# sb-sonata-ethmac.net
KiCad netlist of a schematic drawn in Altium Designer
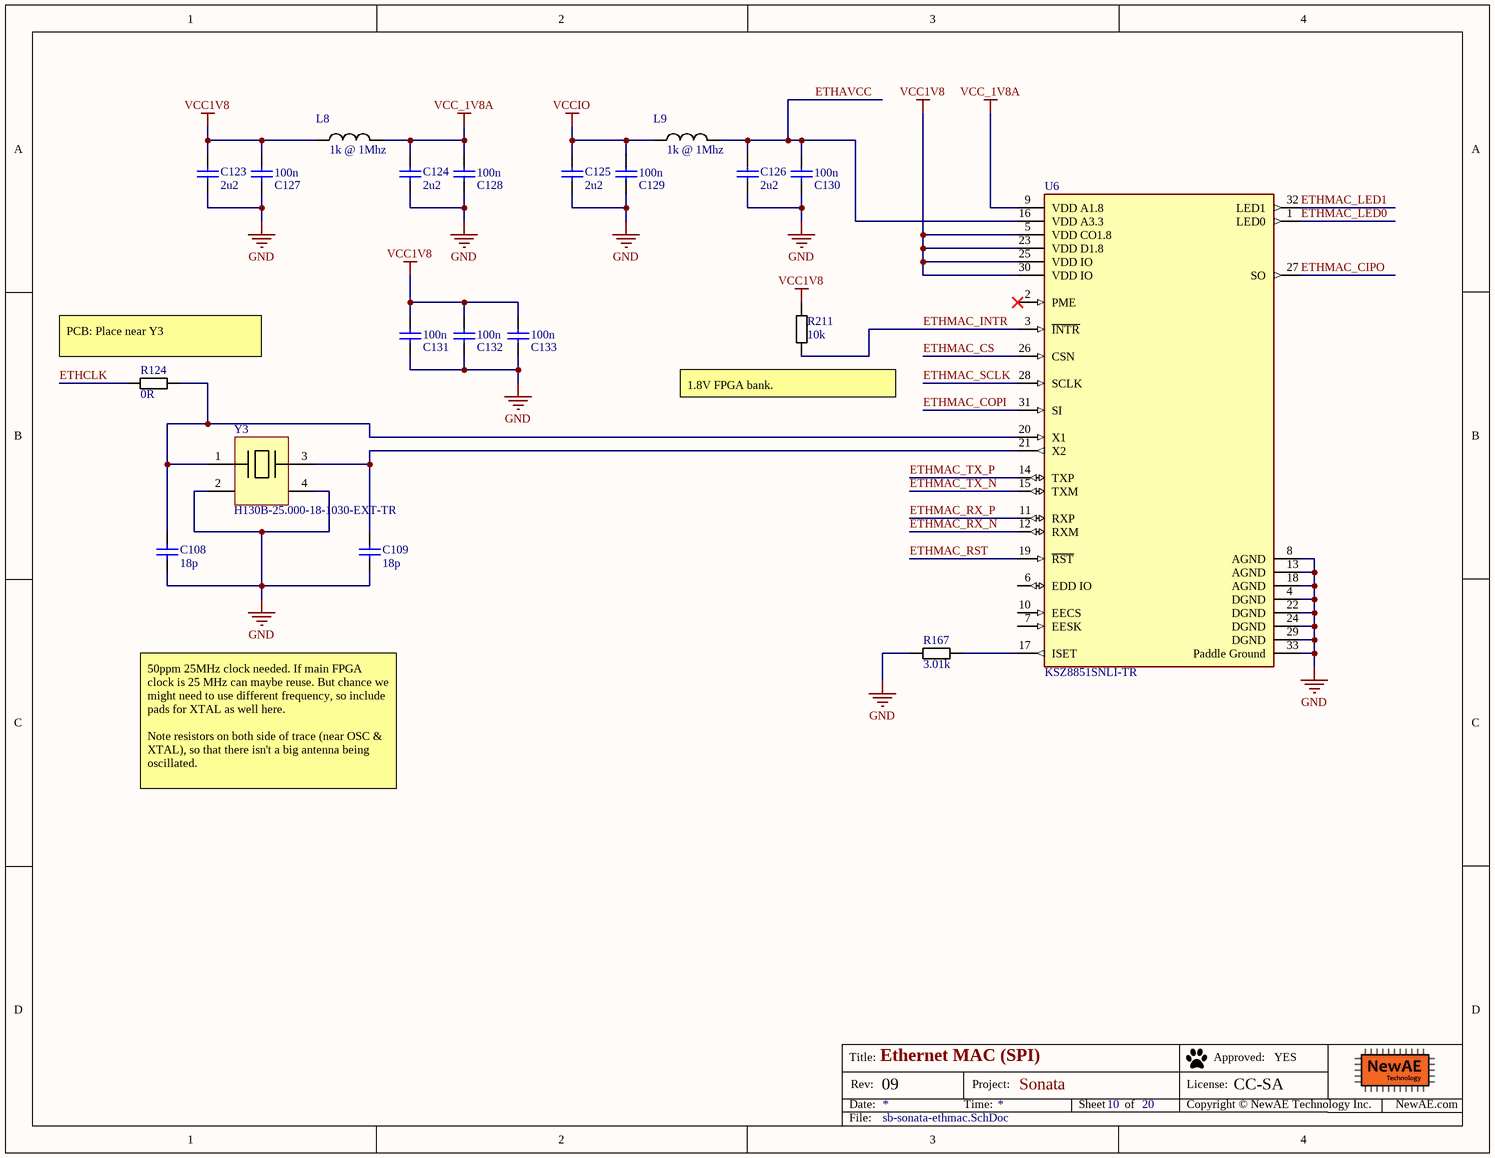
[diagram p0: sb-sonata-ethmac.SchDoc]

(export (version "E")
  (design (tool "Eeschema 10.0.6"))
  (components
    (comp (ref "C108")
      (value "18p")
      (footprint "CAPC0402_M")
      (description "18p, 0402")
      (fields (field (name "PART NUMBER") "CCHIP-18p-0402"))
      (libsource (lib "NewAE_AltiumLib") (part "CAP"))
    )
    (comp (ref "C109")
      (value "18p")
      (footprint "CAPC0402_M")
      (description "18p, 0402")
      (fields (field (name "PART NUMBER") "CCHIP-18p-0402"))
      (libsource (lib "NewAE_AltiumLib") (part "CAP"))
    )
    (comp (ref "C123")
      (value "2u2")
      (footprint "CAPC0603_M")
      (description "2u2, 0603")
      (fields (field (name "PART NUMBER") "CCHIP-2u2-0603"))
      (libsource (lib "NewAE_AltiumLib") (part "CAP"))
    )
    (comp (ref "C124")
      (value "2u2")
      (footprint "CAPC0603_M")
      (description "2u2, 0603")
      (fields (field (name "PART NUMBER") "CCHIP-2u2-0603"))
      (libsource (lib "NewAE_AltiumLib") (part "CAP"))
    )
    (comp (ref "C125")
      (value "2u2")
      (footprint "CAPC0603_M")
      (description "2u2, 0603")
      (fields (field (name "PART NUMBER") "CCHIP-2u2-0603"))
      (libsource (lib "NewAE_AltiumLib") (part "CAP"))
    )
    (comp (ref "C126")
      (value "2u2")
      (footprint "CAPC0603_M")
      (description "2u2, 0603")
      (fields (field (name "PART NUMBER") "CCHIP-2u2-0603"))
      (libsource (lib "NewAE_AltiumLib") (part "CAP"))
    )
    (comp (ref "C127")
      (value "100n")
      (footprint "CAPC0402_M")
      (description "100n, 0402")
      (fields (field (name "PART NUMBER") "CCHIP-100n-0402"))
      (libsource (lib "NewAE_AltiumLib") (part "CAP"))
    )
    (comp (ref "C128")
      (value "100n")
      (footprint "CAPC0402_M")
      (description "100n, 0402")
      (fields (field (name "PART NUMBER") "CCHIP-100n-0402"))
      (libsource (lib "NewAE_AltiumLib") (part "CAP"))
    )
    (comp (ref "C129")
      (value "100n")
      (footprint "CAPC0402_M")
      (description "100n, 0402")
      (fields (field (name "PART NUMBER") "CCHIP-100n-0402"))
      (libsource (lib "NewAE_AltiumLib") (part "CAP"))
    )
    (comp (ref "C130")
      (value "100n")
      (footprint "CAPC0402_M")
      (description "100n, 0402")
      (fields (field (name "PART NUMBER") "CCHIP-100n-0402"))
      (libsource (lib "NewAE_AltiumLib") (part "CAP"))
    )
    (comp (ref "C131")
      (value "100n")
      (footprint "CAPC0402_M")
      (description "100n, 0402")
      (fields (field (name "PART NUMBER") "CCHIP-100n-0402"))
      (libsource (lib "NewAE_AltiumLib") (part "CAP"))
    )
    (comp (ref "C132")
      (value "100n")
      (footprint "CAPC0402_M")
      (description "100n, 0402")
      (fields (field (name "PART NUMBER") "CCHIP-100n-0402"))
      (libsource (lib "NewAE_AltiumLib") (part "CAP"))
    )
    (comp (ref "C133")
      (value "100n")
      (footprint "CAPC0402_M")
      (description "100n, 0402")
      (fields (field (name "PART NUMBER") "CCHIP-100n-0402"))
      (libsource (lib "NewAE_AltiumLib") (part "CAP"))
    )
    (comp (ref "L8")
      (value "1k @ 1Mhz")
      (footprint "IND_0603")
      (description "Ferrite Beads HI CUR CHIP BD 0603 1000OHMS 25%")
      (fields (field (name "PART NUMBER") "FBCHIP-1k-0603"))
      (libsource (lib "NewAE_AltiumLib") (part "IND"))
    )
    (comp (ref "L9")
      (value "1k @ 1Mhz")
      (footprint "IND_0603")
      (description "Ferrite Beads HI CUR CHIP BD 0603 1000OHMS 25%")
      (fields (field (name "PART NUMBER") "FBCHIP-1k-0603"))
      (libsource (lib "NewAE_AltiumLib") (part "IND"))
    )
    (comp (ref "R124")
      (value "0R")
      (footprint "RESC1608X55N")
      (description "0R, 0603, 1/10W")
      (fields (field (name "PART NUMBER") "RCHIP-0R-0603") (field (name "TOLERANCE") "1%"))
      (libsource (lib "NewAE_AltiumLib") (part "RES-EU"))
    )
    (comp (ref "R167")
      (value "3.01k")
      (footprint "RESC1005X40N")
      (description "3k01 res, 0402, 1%, 1/16W")
      (fields (field (name "PART NUMBER") "RCHIP-3K01-0402") (field (name "TOLERANCE") "1%"))
      (libsource (lib "NewAE_AltiumLib") (part "RES-EU"))
    )
    (comp (ref "R211")
      (value "10k")
      (footprint "RESC1005X40N")
      (description "10k res, 0402, 1%, 1/16W")
      (fields (field (name "PART NUMBER") "RCHIP-10K-0402") (field (name "TOLERANCE") "1%"))
      (libsource (lib "") (part "RES-EU_1"))
    )
    (comp (ref "U6")
      (value "KSZ8851SNLI-TR")
      (footprint "FP-QFN55-32LD-PL-5-IPC_C")
      (description "IC ETHERNET CTLR 1PORT PCI 32MLF")
      (libsource (lib "Altium Content Vault") (part "1954b1b3eed228fd5e2ba5f863c4309"))
    )
    (comp (ref "Y3")
      (value "H130B-12.000-16-2525-EXT-TR")
      (footprint "5x3.2MM XTAL")
      (description "12MHz ±25ppm Crystal 16pF 35 Ohms 4-SMD, No Lead")
      (fields
        (field (name "MANUFACTURER PART NUMBER") "H130B-25.000-18-1030-EXT-TR")
        (field (name "PART NUMBER") "H130B-25.000-18-1030-EXT-TR")
      )
      (libsource (lib "NewAE_AltiumLib") (part "H130B-12.000-16-2525-EXT-TR"))
    )
  )
  (nets
    (net (code "1") (name "/ETHAVCC") (class "Default")
      (node (ref "C126") (pin "1") (pinfunction "1_1") (pintype "passive"))
      (node (ref "C130") (pin "1") (pinfunction "1_1") (pintype "passive"))
      (node (ref "L9") (pin "2") (pinfunction "2_2") (pintype "passive"))
      (node (ref "U6") (pin "16") (pinfunction "VDD_A3.3_16") (pintype "power_in"))
    )
    (net (code "2") (name "/ETHCLK") (class "Default")
      (node (ref "R124") (pin "1") (pinfunction "1_1") (pintype "passive"))
    )
    (net (code "3") (name "/ETHMAC_CIPO") (class "Default")
      (node (ref "U6") (pin "27") (pinfunction "SO_27") (pintype "output"))
    )
    (net (code "4") (name "/ETHMAC_COPI") (class "Default")
      (node (ref "U6") (pin "31") (pinfunction "SI_31") (pintype "input"))
    )
    (net (code "5") (name "/ETHMAC_CS") (class "Default")
      (node (ref "U6") (pin "26") (pinfunction "CSN_26") (pintype "input"))
    )
    (net (code "6") (name "/ETHMAC_INTR") (class "Default")
      (node (ref "R211") (pin "2") (pinfunction "2_2") (pintype "passive"))
      (node (ref "U6") (pin "3") (pinfunction "~{INTR}_3") (pintype "input"))
    )
    (net (code "7") (name "/ETHMAC_LED0") (class "Default")
      (node (ref "U6") (pin "1") (pinfunction "LED0_1") (pintype "output"))
    )
    (net (code "8") (name "/ETHMAC_LED1") (class "Default")
      (node (ref "U6") (pin "32") (pinfunction "LED1_32") (pintype "output"))
    )
    (net (code "9") (name "/ETHMAC_RST") (class "Default")
      (node (ref "U6") (pin "19") (pinfunction "~{RST}_19") (pintype "input"))
    )
    (net (code "10") (name "/ETHMAC_RX_N") (class "Default")
      (node (ref "U6") (pin "12") (pinfunction "RXM_12") (pintype "bidirectional"))
    )
    (net (code "11") (name "/ETHMAC_RX_P") (class "Default")
      (node (ref "U6") (pin "11") (pinfunction "RXP_11") (pintype "bidirectional"))
    )
    (net (code "12") (name "/ETHMAC_SCLK") (class "Default")
      (node (ref "U6") (pin "28") (pinfunction "SCLK_28") (pintype "input"))
    )
    (net (code "13") (name "/ETHMAC_TX_N") (class "Default")
      (node (ref "U6") (pin "15") (pinfunction "TXM_15") (pintype "bidirectional"))
    )
    (net (code "14") (name "/ETHMAC_TX_P") (class "Default")
      (node (ref "U6") (pin "14") (pinfunction "TXP_14") (pintype "bidirectional"))
    )
    (net (code "15") (name "GND") (class "Default")
      (node (ref "C108") (pin "2") (pinfunction "2_2") (pintype "passive"))
      (node (ref "C109") (pin "2") (pinfunction "2_2") (pintype "passive"))
      (node (ref "C123") (pin "2") (pinfunction "2_2") (pintype "passive"))
      (node (ref "C124") (pin "2") (pinfunction "2_2") (pintype "passive"))
      (node (ref "C125") (pin "2") (pinfunction "2_2") (pintype "passive"))
      (node (ref "C126") (pin "2") (pinfunction "2_2") (pintype "passive"))
      (node (ref "C127") (pin "2") (pinfunction "2_2") (pintype "passive"))
      (node (ref "C128") (pin "2") (pinfunction "2_2") (pintype "passive"))
      (node (ref "C129") (pin "2") (pinfunction "2_2") (pintype "passive"))
      (node (ref "C130") (pin "2") (pinfunction "2_2") (pintype "passive"))
      (node (ref "C131") (pin "2") (pinfunction "2_2") (pintype "passive"))
      (node (ref "C132") (pin "2") (pinfunction "2_2") (pintype "passive"))
      (node (ref "C133") (pin "2") (pinfunction "2_2") (pintype "passive"))
      (node (ref "R167") (pin "1") (pinfunction "1_1") (pintype "passive"))
      (node (ref "U6") (pin "13") (pinfunction "AGND_13") (pintype "power_in"))
      (node (ref "U6") (pin "18") (pinfunction "AGND_18") (pintype "power_in"))
      (node (ref "U6") (pin "22") (pinfunction "DGND_22") (pintype "power_in"))
      (node (ref "U6") (pin "24") (pinfunction "DGND_24") (pintype "power_in"))
      (node (ref "U6") (pin "29") (pinfunction "DGND_29") (pintype "power_in"))
      (node (ref "U6") (pin "33") (pinfunction "Paddle_Ground_33") (pintype "passive"))
      (node (ref "U6") (pin "4") (pinfunction "DGND_4") (pintype "power_in"))
      (node (ref "U6") (pin "8") (pinfunction "AGND_8") (pintype "power_in"))
      (node (ref "Y3") (pin "2") (pinfunction "2_2") (pintype "passive"))
      (node (ref "Y3") (pin "4") (pinfunction "4_4") (pintype "passive"))
    )
    (net (code "16") (name "Net-(U6-ISET)") (class "Default")
      (node (ref "R167") (pin "2") (pinfunction "2_2") (pintype "passive"))
      (node (ref "U6") (pin "17") (pinfunction "ISET_17") (pintype "output"))
    )
    (net (code "17") (name "Net-(U6-X1)") (class "Default")
      (node (ref "C108") (pin "1") (pinfunction "1_1") (pintype "passive"))
      (node (ref "R124") (pin "2") (pinfunction "2_2") (pintype "passive"))
      (node (ref "U6") (pin "20") (pinfunction "X1_20") (pintype "input"))
      (node (ref "Y3") (pin "1") (pinfunction "1_1") (pintype "passive"))
    )
    (net (code "18") (name "Net-(U6-X2)") (class "Default")
      (node (ref "C109") (pin "1") (pinfunction "1_1") (pintype "passive"))
      (node (ref "U6") (pin "21") (pinfunction "X2_21") (pintype "output"))
      (node (ref "Y3") (pin "3") (pinfunction "3_3") (pintype "passive"))
    )
    (net (code "19") (name "VCC1V8") (class "Default")
      (node (ref "C123") (pin "1") (pinfunction "1_1") (pintype "passive"))
      (node (ref "C127") (pin "1") (pinfunction "1_1") (pintype "passive"))
      (node (ref "C131") (pin "1") (pinfunction "1_1") (pintype "passive"))
      (node (ref "C132") (pin "1") (pinfunction "1_1") (pintype "passive"))
      (node (ref "C133") (pin "1") (pinfunction "1_1") (pintype "passive"))
      (node (ref "L8") (pin "1") (pinfunction "1_1") (pintype "passive"))
      (node (ref "R211") (pin "1") (pinfunction "1_1") (pintype "passive"))
      (node (ref "U6") (pin "23") (pinfunction "VDD_D1.8_23") (pintype "power_in"))
      (node (ref "U6") (pin "25") (pinfunction "VDD_IO_25") (pintype "power_in"))
      (node (ref "U6") (pin "30") (pinfunction "VDD_IO_30") (pintype "power_in"))
      (node (ref "U6") (pin "5") (pinfunction "VDD_CO1.8_5") (pintype "power_in"))
    )
    (net (code "20") (name "VCCIO") (class "Default")
      (node (ref "C125") (pin "1") (pinfunction "1_1") (pintype "passive"))
      (node (ref "C129") (pin "1") (pinfunction "1_1") (pintype "passive"))
      (node (ref "L9") (pin "1") (pinfunction "1_1") (pintype "passive"))
    )
    (net (code "21") (name "VCC_1V8A") (class "Default")
      (node (ref "C124") (pin "1") (pinfunction "1_1") (pintype "passive"))
      (node (ref "C128") (pin "1") (pinfunction "1_1") (pintype "passive"))
      (node (ref "L8") (pin "2") (pinfunction "2_2") (pintype "passive"))
      (node (ref "U6") (pin "9") (pinfunction "VDD_A1.8_9") (pintype "power_in"))
    )
    (net (code "22") (name "unconnected-(U6-EDD_IO-Pad6)") (class "Default")
      (node (ref "U6") (pin "6") (pinfunction "EDD_IO_6") (pintype "bidirectional"))
    )
    (net (code "23") (name "unconnected-(U6-EECS-Pad10)") (class "Default")
      (node (ref "U6") (pin "10") (pinfunction "EECS_10") (pintype "input"))
    )
    (net (code "24") (name "unconnected-(U6-EESK-Pad7)") (class "Default")
      (node (ref "U6") (pin "7") (pinfunction "EESK_7") (pintype "input"))
    )
    (net (code "25") (name "unconnected-(U6-PME-Pad2)") (class "Default")
      (node (ref "U6") (pin "2") (pinfunction "PME_2") (pintype "input+no_connect"))
    )
  )
)
